# raspi.net
KiCad netlist of a schematic drawn in Altium Designer
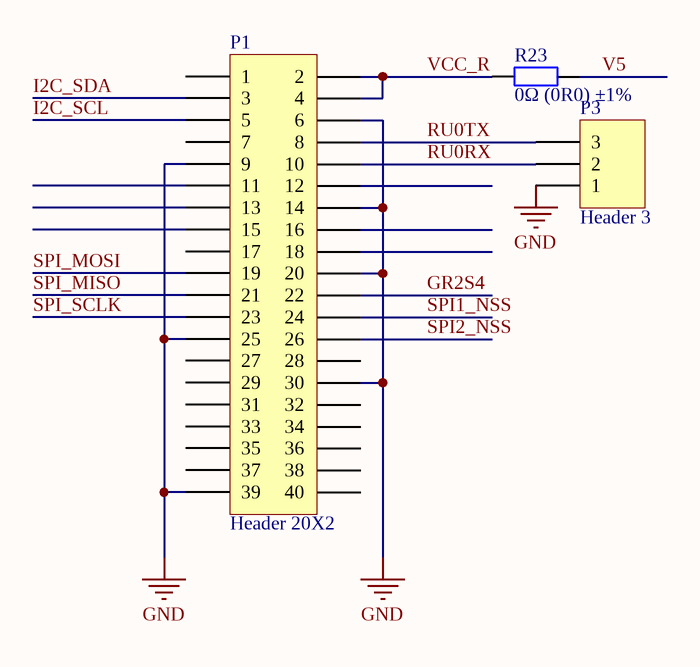
[diagram p0: raspi.SchDoc]

(export (version "E")
  (design (tool "Eeschema 10.0.6"))
  (components
    (comp (ref "P1")
      (value "Header 20X2")
      (footprint "HDR2X20")
      (description "Header, 20-Pin, Dual row")
      (fields (field (name "PUBLISHER") "Altium Limited"))
      (libsource (lib "Miscellaneous Connectors") (part "Header 20X2"))
    )
    (comp (ref "P3")
      (value "Header 3")
      (footprint "HDR1X3")
      (description "Header, 3-Pin")
      (fields (field (name "PUBLISHER") "Altium Limited"))
      (libsource (lib "Miscellaneous Connectors") (part "Header 3"))
    )
    (comp (ref "R23")
      (value "0Ω (0R0) ±1%")
      (footprint "1206_R")
      (description "贴片电阻")
      (libsource (lib "Miscellaneous Devices LC") (part "1206 0Ω (0R0) 1%"))
    )
  )
  (nets
    (net (code "1") (name "/GR2S4") (class "Default")
      (node (ref "P1") (pin "22") (pinfunction "22_22") (pintype "passive"))
    )
    (net (code "2") (name "/I2C_SCL") (class "Default")
      (node (ref "P1") (pin "5") (pinfunction "5_5") (pintype "passive"))
    )
    (net (code "3") (name "/I2C_SDA") (class "Default")
      (node (ref "P1") (pin "3") (pinfunction "3_3") (pintype "passive"))
    )
    (net (code "4") (name "/RU0RX") (class "Default")
      (node (ref "P1") (pin "10") (pinfunction "10_10") (pintype "passive"))
      (node (ref "P3") (pin "2") (pinfunction "2_2") (pintype "passive"))
    )
    (net (code "5") (name "/RU0TX") (class "Default")
      (node (ref "P1") (pin "8") (pinfunction "8_8") (pintype "passive"))
      (node (ref "P3") (pin "3") (pinfunction "3_3") (pintype "passive"))
    )
    (net (code "6") (name "/SPI1_NSS") (class "Default")
      (node (ref "P1") (pin "24") (pinfunction "24_24") (pintype "passive"))
    )
    (net (code "7") (name "/SPI2_NSS") (class "Default")
      (node (ref "P1") (pin "26") (pinfunction "26_26") (pintype "passive"))
    )
    (net (code "8") (name "/SPI_MISO") (class "Default")
      (node (ref "P1") (pin "21") (pinfunction "21_21") (pintype "passive"))
    )
    (net (code "9") (name "/SPI_MOSI") (class "Default")
      (node (ref "P1") (pin "19") (pinfunction "19_19") (pintype "passive"))
    )
    (net (code "10") (name "/SPI_SCLK") (class "Default")
      (node (ref "P1") (pin "23") (pinfunction "23_23") (pintype "passive"))
    )
    (net (code "11") (name "/V5") (class "Default")
      (node (ref "R23") (pin "2") (pinfunction "2_2") (pintype "passive"))
    )
    (net (code "12") (name "/VCC_R") (class "Default")
      (node (ref "P1") (pin "2") (pinfunction "2_2") (pintype "passive"))
      (node (ref "P1") (pin "4") (pinfunction "4_4") (pintype "passive"))
      (node (ref "R23") (pin "1") (pinfunction "1_1") (pintype "passive"))
    )
    (net (code "13") (name "GND") (class "Default")
      (node (ref "P1") (pin "14") (pinfunction "14_14") (pintype "passive"))
      (node (ref "P1") (pin "20") (pinfunction "20_20") (pintype "passive"))
      (node (ref "P1") (pin "25") (pinfunction "25_25") (pintype "passive"))
      (node (ref "P1") (pin "30") (pinfunction "30_30") (pintype "passive"))
      (node (ref "P1") (pin "39") (pinfunction "39_39") (pintype "passive"))
      (node (ref "P1") (pin "6") (pinfunction "6_6") (pintype "passive"))
      (node (ref "P1") (pin "9") (pinfunction "9_9") (pintype "passive"))
      (node (ref "P3") (pin "1") (pinfunction "1_1") (pintype "passive"))
    )
    (net (code "14") (name "unconnected-(P1-Pad1)") (class "Default")
      (node (ref "P1") (pin "1") (pinfunction "1_1") (pintype "passive"))
    )
    (net (code "15") (name "unconnected-(P1-Pad7)") (class "Default")
      (node (ref "P1") (pin "7") (pinfunction "7_7") (pintype "passive"))
    )
    (net (code "16") (name "unconnected-(P1-Pad11)") (class "Default")
      (node (ref "P1") (pin "11") (pinfunction "11_11") (pintype "passive"))
    )
    (net (code "17") (name "unconnected-(P1-Pad12)") (class "Default")
      (node (ref "P1") (pin "12") (pinfunction "12_12") (pintype "passive"))
    )
    (net (code "18") (name "unconnected-(P1-Pad13)") (class "Default")
      (node (ref "P1") (pin "13") (pinfunction "13_13") (pintype "passive"))
    )
    (net (code "19") (name "unconnected-(P1-Pad15)") (class "Default")
      (node (ref "P1") (pin "15") (pinfunction "15_15") (pintype "passive"))
    )
    (net (code "20") (name "unconnected-(P1-Pad16)") (class "Default")
      (node (ref "P1") (pin "16") (pinfunction "16_16") (pintype "passive"))
    )
    (net (code "21") (name "unconnected-(P1-Pad17)") (class "Default")
      (node (ref "P1") (pin "17") (pinfunction "17_17") (pintype "passive"))
    )
    (net (code "22") (name "unconnected-(P1-Pad18)") (class "Default")
      (node (ref "P1") (pin "18") (pinfunction "18_18") (pintype "passive"))
    )
    (net (code "23") (name "unconnected-(P1-Pad27)") (class "Default")
      (node (ref "P1") (pin "27") (pinfunction "27_27") (pintype "passive"))
    )
    (net (code "24") (name "unconnected-(P1-Pad28)") (class "Default")
      (node (ref "P1") (pin "28") (pinfunction "28_28") (pintype "passive"))
    )
    (net (code "25") (name "unconnected-(P1-Pad29)") (class "Default")
      (node (ref "P1") (pin "29") (pinfunction "29_29") (pintype "passive"))
    )
    (net (code "26") (name "unconnected-(P1-Pad31)") (class "Default")
      (node (ref "P1") (pin "31") (pinfunction "31_31") (pintype "passive"))
    )
    (net (code "27") (name "unconnected-(P1-Pad32)") (class "Default")
      (node (ref "P1") (pin "32") (pinfunction "32_32") (pintype "passive"))
    )
    (net (code "28") (name "unconnected-(P1-Pad33)") (class "Default")
      (node (ref "P1") (pin "33") (pinfunction "33_33") (pintype "passive"))
    )
    (net (code "29") (name "unconnected-(P1-Pad34)") (class "Default")
      (node (ref "P1") (pin "34") (pinfunction "34_34") (pintype "passive"))
    )
    (net (code "30") (name "unconnected-(P1-Pad35)") (class "Default")
      (node (ref "P1") (pin "35") (pinfunction "35_35") (pintype "passive"))
    )
    (net (code "31") (name "unconnected-(P1-Pad36)") (class "Default")
      (node (ref "P1") (pin "36") (pinfunction "36_36") (pintype "passive"))
    )
    (net (code "32") (name "unconnected-(P1-Pad37)") (class "Default")
      (node (ref "P1") (pin "37") (pinfunction "37_37") (pintype "passive"))
    )
    (net (code "33") (name "unconnected-(P1-Pad38)") (class "Default")
      (node (ref "P1") (pin "38") (pinfunction "38_38") (pintype "passive"))
    )
    (net (code "34") (name "unconnected-(P1-Pad40)") (class "Default")
      (node (ref "P1") (pin "40") (pinfunction "40_40") (pintype "passive"))
    )
  )
)
